# ESC_MCU.net
KiCad netlist of a schematic drawn in Altium Designer
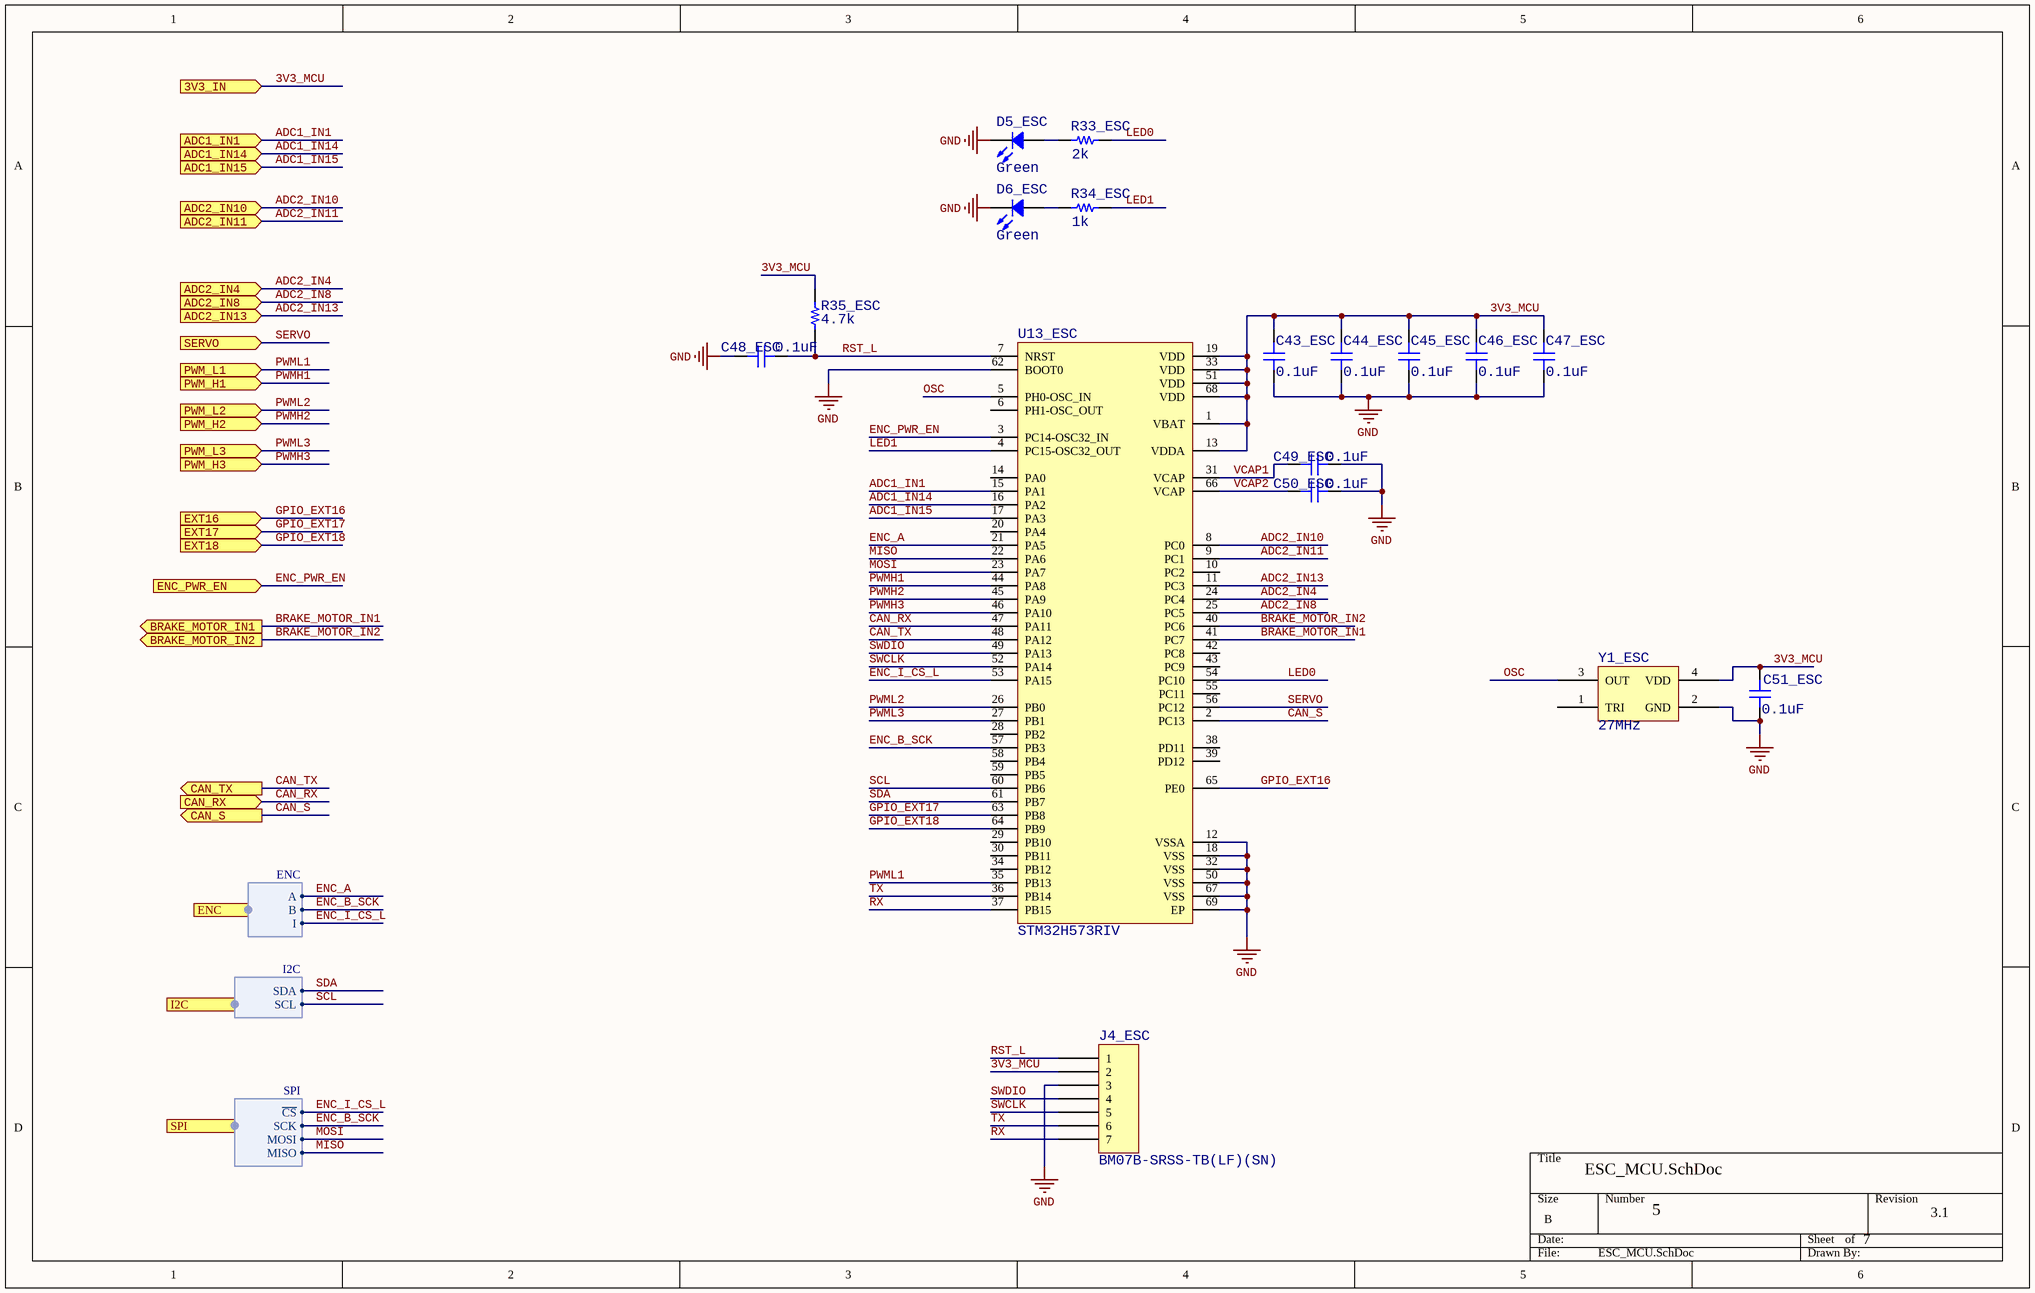
[diagram p0: ESC_MCU.SchDoc]

(export (version "E")
  (design (tool "Eeschema 10.0.6"))
  (components
    (comp (ref "C43_ESC")
      (value "0.1uF")
      (footprint "CAP_0402")
      (description "CAP CER 402")
      (libsource (lib "IC") (part "CAP_0402"))
    )
    (comp (ref "C44_ESC")
      (value "0.1uF")
      (footprint "CAP_0402")
      (description "CAP CER 402")
      (libsource (lib "IC") (part "CAP_0402"))
    )
    (comp (ref "C45_ESC")
      (value "0.1uF")
      (footprint "CAP_0402")
      (description "CAP CER 402")
      (libsource (lib "IC") (part "CAP_0402"))
    )
    (comp (ref "C46_ESC")
      (value "0.1uF")
      (footprint "CAP_0402")
      (description "CAP CER 402")
      (libsource (lib "IC") (part "CAP_0402"))
    )
    (comp (ref "C47_ESC")
      (value "0.1uF")
      (footprint "CAP_0402")
      (description "CAP CER 402")
      (libsource (lib "IC") (part "CAP_0402"))
    )
    (comp (ref "C48_ESC")
      (value "0.1uF")
      (footprint "CAP_0402")
      (description "CAP CER 402")
      (libsource (lib "IC") (part "CAP_0402"))
    )
    (comp (ref "C49_ESC")
      (value "0.1uF")
      (footprint "CAP_0402")
      (description "CAP CER 402")
      (libsource (lib "IC") (part "CAP_0402"))
    )
    (comp (ref "C50_ESC")
      (value "0.1uF")
      (footprint "CAP_0402")
      (description "CAP CER 402")
      (libsource (lib "IC") (part "CAP_0402"))
    )
    (comp (ref "C51_ESC")
      (value "0.1uF")
      (footprint "CAP_0402")
      (description "CAP CER 402")
      (libsource (lib "IC") (part "CAP_0402"))
    )
    (comp (ref "D5_ESC")
      (value "Green")
      (footprint "LED 0603_1608 GREEN")
      (description "LED GREEN CLEAR 2SMD")
      (fields (field (name "PART NUMBER") "XZCDGK53W-8VF") (field (name "MANUFACTURER") "SunLED"))
      (libsource (lib "Celestial Altium Library - altium_library") (part "LED"))
    )
    (comp (ref "D6_ESC")
      (value "Green")
      (footprint "LED 0603_1608 GREEN")
      (description "LED GREEN CLEAR 2SMD")
      (fields (field (name "PART NUMBER") "XZCDGK53W-8VF") (field (name "MANUFACTURER") "SunLED"))
      (libsource (lib "Celestial Altium Library - altium_library") (part "LED"))
    )
    (comp (ref "J4_ESC")
      (value "BM07B-SRSS-TB(LF)(SN)")
      (footprint "JST BM07B-SRSS-TB")
      (description "CONN HEADER SMD 7POS 1MM")
      (fields (field (name "MANUFACTURER") "JST Sales America Inc."))
      (libsource (lib "Celestial Altium Library - altium_library") (part "7 Pin"))
    )
    (comp (ref "R33_ESC")
      (value "2k")
      (footprint "RES_0402")
      (description "RES 0402")
      (libsource (lib "IC") (part "RES_0402"))
    )
    (comp (ref "R34_ESC")
      (value "1k")
      (footprint "RES_0402")
      (description "RES 0402")
      (libsource (lib "IC") (part "RES_0402"))
    )
    (comp (ref "R35_ESC")
      (value "4.7k")
      (footprint "RES_0402")
      (description "RES 0402")
      (libsource (lib "IC") (part "RES_0402"))
    )
    (comp (ref "U13_ESC")
      (value "STM32H573RIV")
      (footprint "68-VFQFPN")
      (libsource (lib "IC") (part "STM32H573RIV"))
    )
    (comp (ref "Y1_ESC")
      (value "27MHz")
      (footprint "ABRACON ASD")
      (description "XTAL OSC XO 27.0000MHZ HCMOS SMD")
      (fields (field (name "PART NUMBER") "ASD3-27.000MHZ-EC-T") (field (name "MANUFACTURER") "Abracon LLC"))
      (libsource (lib "Celestial Altium Library - altium_library") (part "Abracon XO ASD"))
    )
  )
  (nets
    (net (code "4") (name "/3V3_MCU") (class "Default")
      (node (ref "C43_ESC") (pin "2") (pinfunction "2_2") (pintype "passive"))
      (node (ref "C44_ESC") (pin "2") (pinfunction "2_2") (pintype "passive"))
      (node (ref "C45_ESC") (pin "2") (pinfunction "2_2") (pintype "passive"))
      (node (ref "C46_ESC") (pin "2") (pinfunction "2_2") (pintype "passive"))
      (node (ref "C47_ESC") (pin "2") (pinfunction "2_2") (pintype "passive"))
      (node (ref "C51_ESC") (pin "2") (pinfunction "2_2") (pintype "passive"))
      (node (ref "J4_ESC") (pin "2") (pinfunction "2_2") (pintype "passive"))
      (node (ref "R35_ESC") (pin "2") (pinfunction "2_2") (pintype "passive"))
      (node (ref "U13_ESC") (pin "1") (pinfunction "VBAT_1") (pintype "passive"))
      (node (ref "U13_ESC") (pin "13") (pinfunction "VDDA_13") (pintype "passive"))
      (node (ref "U13_ESC") (pin "19") (pinfunction "VDD_19") (pintype "passive"))
      (node (ref "U13_ESC") (pin "33") (pinfunction "VDD_33") (pintype "passive"))
      (node (ref "U13_ESC") (pin "51") (pinfunction "VDD_51") (pintype "passive"))
      (node (ref "U13_ESC") (pin "68") (pinfunction "VDD_68") (pintype "passive"))
      (node (ref "Y1_ESC") (pin "4") (pinfunction "VDD_4") (pintype "passive"))
    )
    (net (code "5") (name "/ADC1_IN1") (class "Default")
      (node (ref "U13_ESC") (pin "15") (pinfunction "PA1_15") (pintype "passive"))
    )
    (net (code "6") (name "/ADC1_IN14") (class "Default")
      (node (ref "U13_ESC") (pin "16") (pinfunction "PA2_16") (pintype "passive"))
    )
    (net (code "7") (name "/ADC1_IN15") (class "Default")
      (node (ref "U13_ESC") (pin "17") (pinfunction "PA3_17") (pintype "passive"))
    )
    (net (code "8") (name "/ADC2_IN4") (class "Default")
      (node (ref "U13_ESC") (pin "24") (pinfunction "PC4_24") (pintype "passive"))
    )
    (net (code "9") (name "/ADC2_IN8") (class "Default")
      (node (ref "U13_ESC") (pin "25") (pinfunction "PC5_25") (pintype "passive"))
    )
    (net (code "10") (name "/ADC2_IN10") (class "Default")
      (node (ref "U13_ESC") (pin "8") (pinfunction "PC0_8") (pintype "passive"))
    )
    (net (code "11") (name "/ADC2_IN11") (class "Default")
      (node (ref "U13_ESC") (pin "9") (pinfunction "PC1_9") (pintype "passive"))
    )
    (net (code "12") (name "/ADC2_IN13") (class "Default")
      (node (ref "U13_ESC") (pin "11") (pinfunction "PC3_11") (pintype "passive"))
    )
    (net (code "13") (name "/BRAKE_MOTOR_IN1") (class "Default")
      (node (ref "U13_ESC") (pin "41") (pinfunction "PC7_41") (pintype "passive"))
    )
    (net (code "14") (name "/BRAKE_MOTOR_IN2") (class "Default")
      (node (ref "U13_ESC") (pin "40") (pinfunction "PC6_40") (pintype "passive"))
    )
    (net (code "15") (name "/CAN_RX") (class "Default")
      (node (ref "U13_ESC") (pin "47") (pinfunction "PA11_47") (pintype "passive"))
    )
    (net (code "16") (name "/CAN_S") (class "Default")
      (node (ref "U13_ESC") (pin "2") (pinfunction "PC13_2") (pintype "passive"))
    )
    (net (code "17") (name "/CAN_TX") (class "Default")
      (node (ref "U13_ESC") (pin "48") (pinfunction "PA12_48") (pintype "passive"))
    )
    (net (code "18") (name "/ENC_A") (class "Default")
      (node (ref "U13_ESC") (pin "21") (pinfunction "PA5_21") (pintype "passive"))
    )
    (net (code "19") (name "/ENC_B_SCK") (class "Default")
      (node (ref "U13_ESC") (pin "57") (pinfunction "PB3_57") (pintype "passive"))
    )
    (net (code "20") (name "/ENC_I_CS_L") (class "Default")
      (node (ref "U13_ESC") (pin "53") (pinfunction "PA15_53") (pintype "passive"))
    )
    (net (code "21") (name "/ENC_PWR_EN") (class "Default")
      (node (ref "U13_ESC") (pin "3") (pinfunction "PC14-OSC32_IN_3") (pintype "passive"))
    )
    (net (code "22") (name "/GPIO_EXT16") (class "Default")
      (node (ref "U13_ESC") (pin "65") (pinfunction "PE0_65") (pintype "passive"))
    )
    (net (code "23") (name "/GPIO_EXT17") (class "Default")
      (node (ref "U13_ESC") (pin "63") (pinfunction "PB8_63") (pintype "passive"))
    )
    (net (code "24") (name "/GPIO_EXT18") (class "Default")
      (node (ref "U13_ESC") (pin "64") (pinfunction "PB9_64") (pintype "passive"))
    )
    (net (code "25") (name "/LED0") (class "Default")
      (node (ref "R33_ESC") (pin "2") (pinfunction "2_2") (pintype "passive"))
      (node (ref "U13_ESC") (pin "54") (pinfunction "PC10_54") (pintype "passive"))
    )
    (net (code "26") (name "/LED1") (class "Default")
      (node (ref "R34_ESC") (pin "2") (pinfunction "2_2") (pintype "passive"))
      (node (ref "U13_ESC") (pin "4") (pinfunction "PC15-OSC32_OUT_4") (pintype "passive"))
    )
    (net (code "27") (name "/MISO") (class "Default")
      (node (ref "U13_ESC") (pin "22") (pinfunction "PA6_22") (pintype "passive"))
    )
    (net (code "28") (name "/MOSI") (class "Default")
      (node (ref "U13_ESC") (pin "23") (pinfunction "PA7_23") (pintype "passive"))
    )
    (net (code "29") (name "/OSC") (class "Default")
      (node (ref "U13_ESC") (pin "5") (pinfunction "PH0-OSC_IN_5") (pintype "passive"))
      (node (ref "Y1_ESC") (pin "3") (pinfunction "OUT_3") (pintype "passive"))
    )
    (net (code "30") (name "/PWMH1") (class "Default")
      (node (ref "U13_ESC") (pin "44") (pinfunction "PA8_44") (pintype "passive"))
    )
    (net (code "31") (name "/PWMH2") (class "Default")
      (node (ref "U13_ESC") (pin "45") (pinfunction "PA9_45") (pintype "passive"))
    )
    (net (code "32") (name "/PWMH3") (class "Default")
      (node (ref "U13_ESC") (pin "46") (pinfunction "PA10_46") (pintype "passive"))
    )
    (net (code "33") (name "/PWML1") (class "Default")
      (node (ref "U13_ESC") (pin "35") (pinfunction "PB13_35") (pintype "passive"))
    )
    (net (code "34") (name "/PWML2") (class "Default")
      (node (ref "U13_ESC") (pin "26") (pinfunction "PB0_26") (pintype "passive"))
    )
    (net (code "35") (name "/PWML3") (class "Default")
      (node (ref "U13_ESC") (pin "27") (pinfunction "PB1_27") (pintype "passive"))
    )
    (net (code "36") (name "/RST_L") (class "Default")
      (node (ref "C48_ESC") (pin "1") (pinfunction "1_1") (pintype "passive"))
      (node (ref "J4_ESC") (pin "1") (pinfunction "1_1") (pintype "passive"))
      (node (ref "R35_ESC") (pin "1") (pinfunction "1_1") (pintype "passive"))
      (node (ref "U13_ESC") (pin "7") (pinfunction "NRST_7") (pintype "passive"))
    )
    (net (code "37") (name "/RX") (class "Default")
      (node (ref "J4_ESC") (pin "7") (pinfunction "7_7") (pintype "passive"))
      (node (ref "U13_ESC") (pin "37") (pinfunction "PB15_37") (pintype "passive"))
    )
    (net (code "38") (name "/SCL") (class "Default")
      (node (ref "U13_ESC") (pin "60") (pinfunction "PB6_60") (pintype "passive"))
    )
    (net (code "39") (name "/SDA") (class "Default")
      (node (ref "U13_ESC") (pin "61") (pinfunction "PB7_61") (pintype "passive"))
    )
    (net (code "40") (name "/SERVO") (class "Default")
      (node (ref "U13_ESC") (pin "56") (pinfunction "PC12_56") (pintype "passive"))
    )
    (net (code "41") (name "/SWCLK") (class "Default")
      (node (ref "J4_ESC") (pin "5") (pinfunction "5_5") (pintype "passive"))
      (node (ref "U13_ESC") (pin "52") (pinfunction "PA14_52") (pintype "passive"))
    )
    (net (code "42") (name "/SWDIO") (class "Default")
      (node (ref "J4_ESC") (pin "4") (pinfunction "4_4") (pintype "passive"))
      (node (ref "U13_ESC") (pin "49") (pinfunction "PA13_49") (pintype "passive"))
    )
    (net (code "43") (name "/TX") (class "Default")
      (node (ref "J4_ESC") (pin "6") (pinfunction "6_6") (pintype "passive"))
      (node (ref "U13_ESC") (pin "36") (pinfunction "PB14_36") (pintype "passive"))
    )
    (net (code "44") (name "/VCAP1") (class "Default")
      (node (ref "C49_ESC") (pin "2") (pinfunction "2_2") (pintype "passive"))
      (node (ref "U13_ESC") (pin "31") (pinfunction "VCAP_31") (pintype "passive"))
    )
    (net (code "45") (name "/VCAP2") (class "Default")
      (node (ref "C50_ESC") (pin "2") (pinfunction "2_2") (pintype "passive"))
      (node (ref "U13_ESC") (pin "66") (pinfunction "VCAP_66") (pintype "passive"))
    )
    (net (code "49") (name "GND") (class "Default")
      (node (ref "C43_ESC") (pin "1") (pinfunction "1_1") (pintype "passive"))
      (node (ref "C44_ESC") (pin "1") (pinfunction "1_1") (pintype "passive"))
      (node (ref "C45_ESC") (pin "1") (pinfunction "1_1") (pintype "passive"))
      (node (ref "C46_ESC") (pin "1") (pinfunction "1_1") (pintype "passive"))
      (node (ref "C47_ESC") (pin "1") (pinfunction "1_1") (pintype "passive"))
      (node (ref "C48_ESC") (pin "2") (pinfunction "2_2") (pintype "passive"))
      (node (ref "C49_ESC") (pin "1") (pinfunction "1_1") (pintype "passive"))
      (node (ref "C50_ESC") (pin "1") (pinfunction "1_1") (pintype "passive"))
      (node (ref "C51_ESC") (pin "1") (pinfunction "1_1") (pintype "passive"))
      (node (ref "D5_ESC") (pin "2") (pinfunction "2_2") (pintype "passive"))
      (node (ref "D6_ESC") (pin "2") (pinfunction "2_2") (pintype "passive"))
      (node (ref "J4_ESC") (pin "3") (pinfunction "3_3") (pintype "passive"))
      (node (ref "U13_ESC") (pin "12") (pinfunction "VSSA_12") (pintype "passive"))
      (node (ref "U13_ESC") (pin "18") (pinfunction "VSS_18") (pintype "passive"))
      (node (ref "U13_ESC") (pin "32") (pinfunction "VSS_32") (pintype "passive"))
      (node (ref "U13_ESC") (pin "50") (pinfunction "VSS_50") (pintype "passive"))
      (node (ref "U13_ESC") (pin "62") (pinfunction "BOOT0_62") (pintype "passive"))
      (node (ref "U13_ESC") (pin "67") (pinfunction "VSS_67") (pintype "passive"))
      (node (ref "U13_ESC") (pin "69") (pinfunction "EP_69") (pintype "passive"))
      (node (ref "Y1_ESC") (pin "2") (pinfunction "GND_2") (pintype "passive"))
    )
    (net (code "50") (name "Net-(D5_ESC-Pad1)") (class "Default")
      (node (ref "D5_ESC") (pin "1") (pinfunction "1_1") (pintype "passive"))
      (node (ref "R33_ESC") (pin "1") (pinfunction "1_1") (pintype "passive"))
    )
    (net (code "51") (name "Net-(D6_ESC-Pad1)") (class "Default")
      (node (ref "D6_ESC") (pin "1") (pinfunction "1_1") (pintype "passive"))
      (node (ref "R34_ESC") (pin "1") (pinfunction "1_1") (pintype "passive"))
    )
    (net (code "52") (name "unconnected-(U13_ESC-PA0-Pad14)") (class "Default")
      (node (ref "U13_ESC") (pin "14") (pinfunction "PA0_14") (pintype "passive"))
    )
    (net (code "53") (name "unconnected-(U13_ESC-PA4-Pad20)") (class "Default")
      (node (ref "U13_ESC") (pin "20") (pinfunction "PA4_20") (pintype "passive"))
    )
    (net (code "54") (name "unconnected-(U13_ESC-PB2-Pad28)") (class "Default")
      (node (ref "U13_ESC") (pin "28") (pinfunction "PB2_28") (pintype "passive"))
    )
    (net (code "55") (name "unconnected-(U13_ESC-PB4-Pad58)") (class "Default")
      (node (ref "U13_ESC") (pin "58") (pinfunction "PB4_58") (pintype "passive"))
    )
    (net (code "56") (name "unconnected-(U13_ESC-PB5-Pad59)") (class "Default")
      (node (ref "U13_ESC") (pin "59") (pinfunction "PB5_59") (pintype "passive"))
    )
    (net (code "57") (name "unconnected-(U13_ESC-PB10-Pad29)") (class "Default")
      (node (ref "U13_ESC") (pin "29") (pinfunction "PB10_29") (pintype "passive"))
    )
    (net (code "58") (name "unconnected-(U13_ESC-PB11-Pad30)") (class "Default")
      (node (ref "U13_ESC") (pin "30") (pinfunction "PB11_30") (pintype "passive"))
    )
    (net (code "59") (name "unconnected-(U13_ESC-PB12-Pad34)") (class "Default")
      (node (ref "U13_ESC") (pin "34") (pinfunction "PB12_34") (pintype "passive"))
    )
    (net (code "60") (name "unconnected-(U13_ESC-PC2-Pad10)") (class "Default")
      (node (ref "U13_ESC") (pin "10") (pinfunction "PC2_10") (pintype "passive"))
    )
    (net (code "61") (name "unconnected-(U13_ESC-PC8-Pad42)") (class "Default")
      (node (ref "U13_ESC") (pin "42") (pinfunction "PC8_42") (pintype "passive"))
    )
    (net (code "62") (name "unconnected-(U13_ESC-PC9-Pad43)") (class "Default")
      (node (ref "U13_ESC") (pin "43") (pinfunction "PC9_43") (pintype "passive"))
    )
    (net (code "63") (name "unconnected-(U13_ESC-PC11-Pad55)") (class "Default")
      (node (ref "U13_ESC") (pin "55") (pinfunction "PC11_55") (pintype "passive"))
    )
    (net (code "64") (name "unconnected-(U13_ESC-PD11-Pad38)") (class "Default")
      (node (ref "U13_ESC") (pin "38") (pinfunction "PD11_38") (pintype "passive"))
    )
    (net (code "65") (name "unconnected-(U13_ESC-PD12-Pad39)") (class "Default")
      (node (ref "U13_ESC") (pin "39") (pinfunction "PD12_39") (pintype "passive"))
    )
    (net (code "66") (name "unconnected-(U13_ESC-PH1-OSC_OUT-Pad6)") (class "Default")
      (node (ref "U13_ESC") (pin "6") (pinfunction "PH1-OSC_OUT_6") (pintype "passive"))
    )
    (net (code "67") (name "unconnected-(Y1_ESC-TRI-Pad1)") (class "Default")
      (node (ref "Y1_ESC") (pin "1") (pinfunction "TRI_1") (pintype "passive"))
    )
  )
)
